# rgb-led-cc-driver-mk-6_0.net
KiCad netlist of a schematic drawn in EAGLE
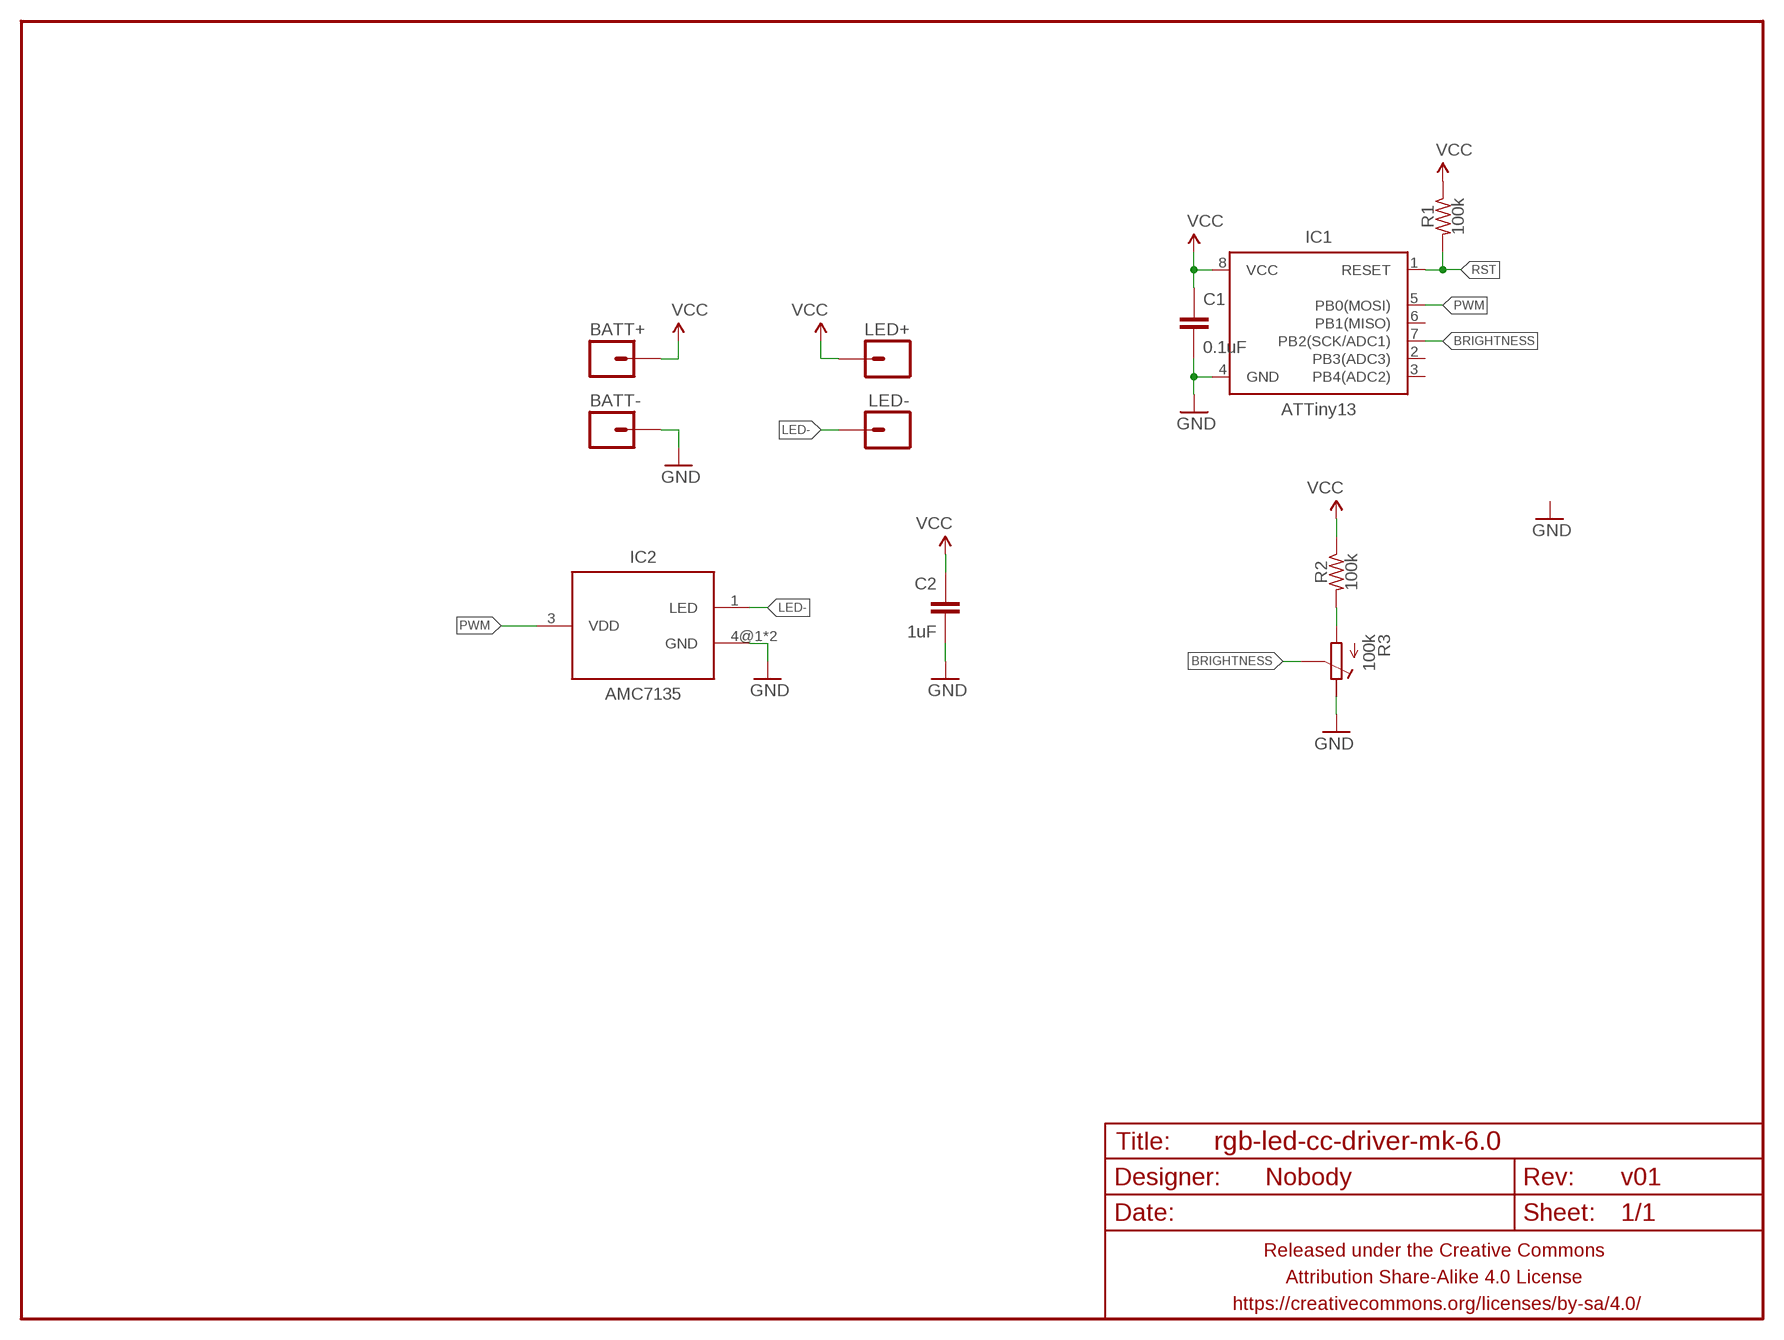
[diagram p0: schematic, sheet 1]

(export (version "E")
  (design (tool "Eeschema 10.0.6"))
  (components
    (comp (ref "BATT+")
      (value "M01NOT-A-VIA-NOPE")
      (footprint "eagle-import:1X01_NOSILK_NOSTOP")
      (libsource (lib "eagle-import") (part "M01NOT-A-VIA-NOPE"))
    )
    (comp (ref "BATT-")
      (value "M01NOT-A-VIA-NOPE")
      (footprint "eagle-import:1X01_NOSILK_NOSTOP")
      (libsource (lib "eagle-import") (part "M01NOT-A-VIA-NOPE"))
    )
    (comp (ref "C1")
      (value "0.1uF")
      (footprint "eagle-import:C0805")
      (libsource (lib "eagle-import") (part "CAPACITOR-CERAMICC0805"))
    )
    (comp (ref "C2")
      (value "1uF")
      (footprint "eagle-import:C1206")
      (libsource (lib "eagle-import") (part "CAPACITOR-CERAMICC1206"))
    )
    (comp (ref "FRAME1")
      (value "FRAME-LETTERNO_PACKAGE")
      (footprint "eagle-import:DUMMY")
      (fields (field (name "DESIGNER") "Nobody"))
      (libsource (lib "eagle-import") (part "FRAME-LETTERNO_PACKAGE"))
    )
    (comp (ref "IC1")
      (value "ATTiny13")
      (footprint "eagle-import:SO08")
      (libsource (lib "eagle-import") (part "ATTINY13SOIC"))
    )
    (comp (ref "IC2")
      (value "AMC7135")
      (footprint "eagle-import:SOT89-NOTHERM")
      (libsource (lib "eagle-import") (part "AMC7135SOT-89-NOTHERM"))
    )
    (comp (ref "LED+")
      (value "M01PTH-1.2MM")
      (footprint "eagle-import:1X01-1.2MM")
      (libsource (lib "eagle-import") (part "M01PTH-1.2MM"))
    )
    (comp (ref "LED-")
      (value "M01PTH-1.2MM-NS")
      (footprint "eagle-import:1X01-1.2MM-NS")
      (libsource (lib "eagle-import") (part "M01PTH-1.2MM-NS"))
    )
    (comp (ref "R1")
      (value "100k")
      (footprint "eagle-import:R0805")
      (libsource (lib "eagle-import") (part "RESISTORR0805"))
    )
    (comp (ref "R2")
      (value "100k")
      (footprint "eagle-import:R0805")
      (libsource (lib "eagle-import") (part "RESISTORR0805"))
    )
    (comp (ref "R3")
      (value "100k")
      (footprint "eagle-import:EVM3Y")
      (libsource (lib "eagle-import") (part "POTENTIOMETEREVM3Y"))
    )
  )
  (nets
    (net (code "1") (name "BRIGHTNESS") (class "Default")
      (node (ref "IC1") (pin "7") (pinfunction "PB2(SCK/ADC1)_7") (pintype "bidirectional"))
      (node (ref "R3") (pin "S") (pinfunction "S_S") (pintype "passive"))
    )
    (net (code "2") (name "GND") (class "Default")
      (node (ref "BATT-") (pin "P$1") (pinfunction "1_P$1") (pintype "passive"))
      (node (ref "C1") (pin "2") (pinfunction "2_2") (pintype "passive"))
      (node (ref "C2") (pin "2") (pinfunction "2_2") (pintype "passive"))
      (node (ref "IC1") (pin "4") (pinfunction "GND_4") (pintype "bidirectional"))
      (node (ref "IC2") (pin "4@1") (pinfunction "GND_4@1") (pintype "bidirectional"))
      (node (ref "IC2") (pin "4@2") (pinfunction "GND_4@2") (pintype "bidirectional"))
      (node (ref "R3") (pin "E") (pinfunction "E_E") (pintype "passive"))
    )
    (net (code "3") (name "LED-") (class "Default")
      (node (ref "IC2") (pin "1") (pinfunction "LED_1") (pintype "bidirectional"))
      (node (ref "LED-") (pin "P$1") (pinfunction "1_P$1") (pintype "passive"))
    )
    (net (code "4") (name "Net-(R2-Pad2)") (class "Default")
      (node (ref "R2") (pin "2") (pinfunction "2_2") (pintype "passive"))
      (node (ref "R3") (pin "A") (pinfunction "A_A") (pintype "passive"))
    )
    (net (code "5") (name "PWM") (class "Default")
      (node (ref "IC1") (pin "5") (pinfunction "PB0(MOSI)_5") (pintype "bidirectional"))
      (node (ref "IC2") (pin "3") (pinfunction "VDD_3") (pintype "bidirectional"))
    )
    (net (code "6") (name "RST") (class "Default")
      (node (ref "IC1") (pin "1") (pinfunction "RESET_1") (pintype "bidirectional"))
      (node (ref "R1") (pin "2") (pinfunction "2_2") (pintype "passive"))
    )
    (net (code "7") (name "VCC") (class "Default")
      (node (ref "BATT+") (pin "P$1") (pinfunction "1_P$1") (pintype "passive"))
      (node (ref "C1") (pin "1") (pinfunction "1_1") (pintype "passive"))
      (node (ref "C2") (pin "1") (pinfunction "1_1") (pintype "passive"))
      (node (ref "IC1") (pin "8") (pinfunction "VCC_8") (pintype "bidirectional"))
      (node (ref "LED+") (pin "P$1") (pinfunction "1_P$1") (pintype "passive"))
      (node (ref "R1") (pin "1") (pinfunction "1_1") (pintype "passive"))
      (node (ref "R2") (pin "1") (pinfunction "1_1") (pintype "passive"))
    )
    (net (code "8") (name "unconnected-(IC1-PB1(MISO)-Pad6)") (class "Default")
      (node (ref "IC1") (pin "6") (pinfunction "PB1(MISO)_6") (pintype "bidirectional"))
    )
    (net (code "9") (name "unconnected-(IC1-PB3(ADC3)-Pad2)") (class "Default")
      (node (ref "IC1") (pin "2") (pinfunction "PB3(ADC3)_2") (pintype "bidirectional"))
    )
    (net (code "10") (name "unconnected-(IC1-PB4(ADC2)-Pad3)") (class "Default")
      (node (ref "IC1") (pin "3") (pinfunction "PB4(ADC2)_3") (pintype "bidirectional"))
    )
  )
)
